# PMIC_USB.net
KiCad netlist of a schematic drawn in Altium Designer
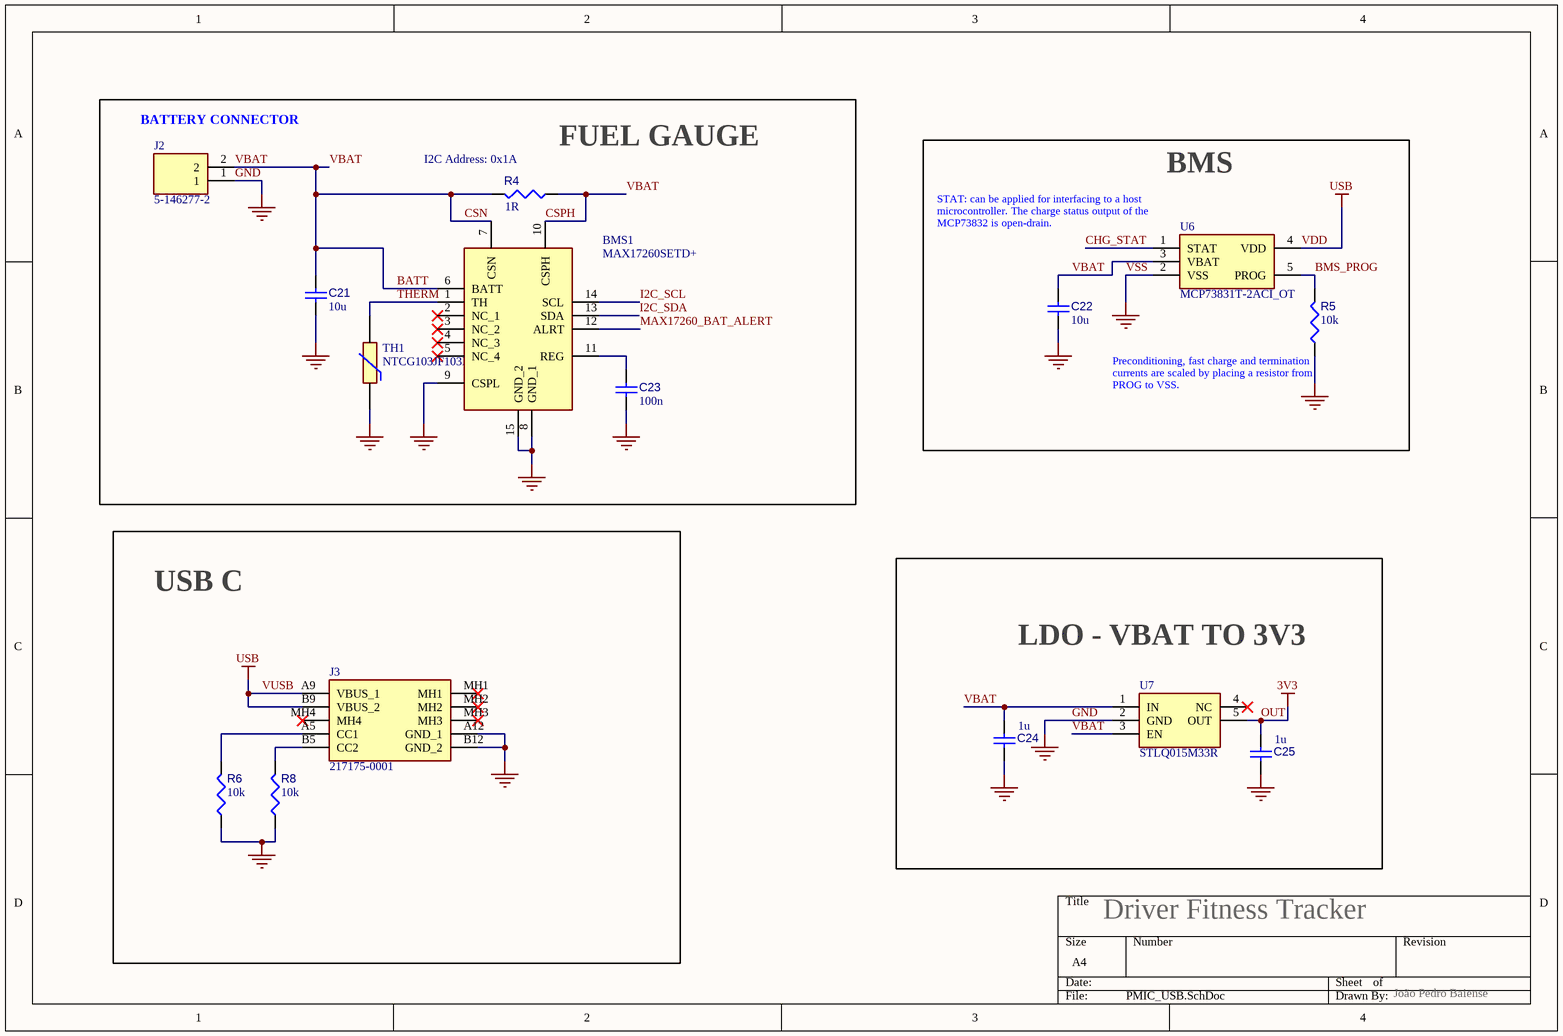
[diagram p0: PMIC_USB.SchDoc]

(export (version "E")
  (design (tool "Eeschema 10.0.6"))
  (components
    (comp (ref "BMS1")
      (value "MAX17260SETD+")
      (footprint "SON40P300X300X80-15N")
      (fields
        (field (name "MOUSER PART NUMBER") "700-MAX17260SETD+")
        (field (name "JLCPCB PART #") "C350946")
      )
      (libsource (lib "Tese_SymbolLib") (part "MAX17260SETD+"))
    )
    (comp (ref "C21")
      (value "10u")
      (footprint "CAPC1608X90X40NL10T20")
      (description "Multilayer Ceramic Capacitors MLCC - SMD/SMT NEW GLOBAL PN KGM15CR51C106MT 0603")
      (fields (field (name "TOLERANCE") "10%") (field (name "JLCPCB PART #") "C19702"))
      (libsource (lib "Tese_project") (part "CAP-NP-2"))
    )
    (comp (ref "C22")
      (value "10u")
      (footprint "CAPC1608X90X40NL10T20")
      (description "Multilayer Ceramic Capacitors MLCC - SMD/SMT NEW GLOBAL PN KGM15CR51C106MT 0603")
      (fields (field (name "TOLERANCE") "10%") (field (name "JLCPCB PART #") "C19702"))
      (libsource (lib "Tese_project") (part "CAP-NP-2"))
    )
    (comp (ref "C23")
      (value "100n")
      (footprint "CAPC1608X90X40NL10T20")
      (description "Multilayer Ceramic Capacitors MLCC - SMD/SMT 50V 0.1 uF X7R 0603 10% AEC-Q200")
      (fields (field (name "TOLERANCE") "10%") (field (name "JLCPCB PART #") "C1523"))
      (libsource (lib "Tese_project") (part "CAP-NP-2"))
    )
    (comp (ref "C24")
      (value "1u")
      (footprint "CAPC1608X90X40NL10T20")
      (description "Multilayer Ceramic Capacitors MLCC - SMD/SMT 50V 1uF X7R 0603 10%")
      (fields (field (name "TOLERANCE") "10%") (field (name "JLCPCB PART #") "C15849"))
      (libsource (lib "Tese_project") (part "CAP-NP-2"))
    )
    (comp (ref "C25")
      (value "1u")
      (footprint "CAPC1608X90X40NL10T20")
      (description "Multilayer Ceramic Capacitors MLCC - SMD/SMT 50V 1uF X7R 0603 10%")
      (fields (field (name "TOLERANCE") "10%") (field (name "JLCPCB PART #") "C15849"))
      (libsource (lib "Tese_project") (part "CAP-NP-2"))
    )
    (comp (ref "J2")
      (value "5-146277-2")
      (footprint "HEADER_2PINS")
      (description "Headers & Wire Housings 2P HEADER GOLD 30u single row")
      (fields (field (name "MOUSER PART NUMBER") "571-5-146277-2"))
      (libsource (lib "Tese_SymbolLib") (part "BATT_CONN_1"))
    )
    (comp (ref "J3")
      (value "217175-0001")
      (footprint "USB_C_CONNECTOR")
      (description "USB Connectors Top-Mnt SMT 6Ckt Type C Rec Molex")
      (fields (field (name "MOUSER PART NUMBER") "538-217175-0001"))
      (libsource (lib "Tese_SymbolLib") (part "USB_C_CONNECTOR"))
    )
    (comp (ref "R4")
      (value "1R")
      (footprint "RESC0402(1005)_L")
      (description "Thin Film Resistors - SMD .1W 1.0ohm 1% 0402 50ppm")
      (fields (field (name "POWER") "63mW") (field (name "TOLERANCE") "1%"))
      (libsource (lib "Tese_project") (part "RES-2"))
    )
    (comp (ref "R5")
      (value "10k")
      (footprint "RESC0402(1005)_L")
      (description "Thin Film Resistors - SMD 1/16W 10K ohm 1% 50ppm")
      (fields (field (name "POWER") "63mW") (field (name "TOLERANCE") "1%"))
      (libsource (lib "Tese_project") (part "RES-2"))
    )
    (comp (ref "R6")
      (value "10k")
      (footprint "RESC0402(1005)_L")
      (description "Thin Film Resistors - SMD 1/16W 10K ohm 1% 50ppm")
      (fields (field (name "POWER") "63mW") (field (name "TOLERANCE") "1%"))
      (libsource (lib "Tese_project") (part "RES-2"))
    )
    (comp (ref "R8")
      (value "10k")
      (footprint "RESC0402(1005)_L")
      (description "Thin Film Resistors - SMD 1/16W 10K ohm 1% 50ppm")
      (fields (field (name "POWER") "63mW") (field (name "TOLERANCE") "1%"))
      (libsource (lib "Tese_project") (part "RES-2"))
    )
    (comp (ref "TH1")
      (value "NTCG103JF103FT1")
      (footprint "THRMC1005X55N")
      (description "NTC (Negative Temperature Coefficient) Thermistors THERMISTOR, NTC 10K OHM, 1%, 0402")
      (fields
        (field (name "MOUSER PART NUMBER") "810-NTCG103JF103FT1")
        (field (name "JLCPCB PART #") "C209959")
      )
      (libsource (lib "Tese_SymbolLib") (part "NTCG103JF103FT1"))
    )
    (comp (ref "U6")
      (value "MCP73831T-2ACI_OT")
      (footprint "SOT95P270X145-5N")
      (description "Battery Management Charge mgnt contr")
      (fields
        (field (name "MOUSER PART NUMBER") "579-MCP73831T-2ACIOT")
        (field (name "ARROW PART NUMBER") "MCP73831T-2ACI/OT")
      )
      (libsource (lib "Tese_SymbolLib") (part "MCP73831T-2ACI_OT"))
    )
    (comp (ref "U7")
      (value "STLQ015M33R")
      (footprint "SOT95P280X145-5N")
      (description "LDO Voltage Regulators 150 mA - ultra low quiescent current linear voltage regulator")
      (fields (field (name "MOUSER PART NUMBER") "511-STLQ015M33R") (field (name "JLCPCB PART #") "C136154"))
      (libsource (lib "Tese_SymbolLib") (part "STLQ015M33R"))
    )
  )
  (nets
    (net (code "1") (name "/BATT") (class "Default")
      (node (ref "BMS1") (pin "10") (pinfunction "CSPH_10") (pintype "passive"))
      (node (ref "BMS1") (pin "6") (pinfunction "BATT_6") (pintype "passive"))
      (node (ref "BMS1") (pin "7") (pinfunction "CSN_7") (pintype "passive"))
      (node (ref "C21") (pin "1") (pinfunction "1_1") (pintype "passive"))
      (node (ref "C22") (pin "1") (pinfunction "1_1") (pintype "passive"))
      (node (ref "C24") (pin "1") (pinfunction "1_1") (pintype "passive"))
      (node (ref "J2") (pin "2") (pinfunction "2_2") (pintype "passive"))
      (node (ref "R4") (pin "1") (pinfunction "1_1") (pintype "passive"))
      (node (ref "R4") (pin "2") (pinfunction "2_2") (pintype "passive"))
      (node (ref "U6") (pin "3") (pinfunction "VBAT_3") (pintype "passive"))
      (node (ref "U7") (pin "1") (pinfunction "IN_1") (pintype "passive"))
      (node (ref "U7") (pin "3") (pinfunction "EN_3") (pintype "passive"))
    )
    (net (code "2") (name "/BMS_PROG") (class "Default")
      (node (ref "R5") (pin "2") (pinfunction "2_2") (pintype "passive"))
      (node (ref "U6") (pin "5") (pinfunction "PROG_5") (pintype "passive"))
    )
    (net (code "3") (name "/CHG_STAT") (class "Default")
      (node (ref "U6") (pin "1") (pinfunction "STAT_1") (pintype "passive"))
    )
    (net (code "4") (name "/I2C_SCL") (class "Default")
      (node (ref "BMS1") (pin "14") (pinfunction "SCL_14") (pintype "passive"))
    )
    (net (code "5") (name "/I2C_SDA") (class "Default")
      (node (ref "BMS1") (pin "13") (pinfunction "SDA_13") (pintype "passive"))
    )
    (net (code "6") (name "/MAX17260_BAT_ALERT") (class "Default")
      (node (ref "BMS1") (pin "12") (pinfunction "ALRT_12") (pintype "passive"))
    )
    (net (code "7") (name "/THERM") (class "Default")
      (node (ref "BMS1") (pin "1") (pinfunction "TH_1") (pintype "passive"))
      (node (ref "TH1") (pin "2") (pinfunction "2_2") (pintype "passive"))
    )
    (net (code "8") (name "3V3") (class "Default")
      (node (ref "C25") (pin "1") (pinfunction "1_1") (pintype "passive"))
      (node (ref "U7") (pin "5") (pinfunction "OUT_5") (pintype "passive"))
    )
    (net (code "9") (name "GND") (class "Default")
      (node (ref "BMS1") (pin "15") (pinfunction "GND_2_15") (pintype "passive"))
      (node (ref "BMS1") (pin "8") (pinfunction "GND_1_8") (pintype "passive"))
      (node (ref "BMS1") (pin "9") (pinfunction "CSPL_9") (pintype "passive"))
      (node (ref "C21") (pin "2") (pinfunction "2_2") (pintype "passive"))
      (node (ref "C22") (pin "2") (pinfunction "2_2") (pintype "passive"))
      (node (ref "C23") (pin "1") (pinfunction "1_1") (pintype "passive"))
      (node (ref "C24") (pin "2") (pinfunction "2_2") (pintype "passive"))
      (node (ref "C25") (pin "2") (pinfunction "2_2") (pintype "passive"))
      (node (ref "J2") (pin "1") (pinfunction "1_1") (pintype "passive"))
      (node (ref "J3") (pin "A12") (pinfunction "GND_1_A12") (pintype "passive"))
      (node (ref "J3") (pin "B12") (pinfunction "GND_2_B12") (pintype "passive"))
      (node (ref "R5") (pin "1") (pinfunction "1_1") (pintype "passive"))
      (node (ref "R6") (pin "1") (pinfunction "1_1") (pintype "passive"))
      (node (ref "R8") (pin "1") (pinfunction "1_1") (pintype "passive"))
      (node (ref "TH1") (pin "1") (pinfunction "1_1") (pintype "passive"))
      (node (ref "U6") (pin "2") (pinfunction "VSS_2") (pintype "passive"))
      (node (ref "U7") (pin "2") (pinfunction "GND_2") (pintype "passive"))
    )
    (net (code "10") (name "Net-(BMS1-REG)") (class "Default")
      (node (ref "BMS1") (pin "11") (pinfunction "REG_11") (pintype "passive"))
      (node (ref "C23") (pin "2") (pinfunction "2_2") (pintype "passive"))
    )
    (net (code "11") (name "Net-(J3-CC1)") (class "Default")
      (node (ref "J3") (pin "A5") (pinfunction "CC1_A5") (pintype "passive"))
      (node (ref "R6") (pin "2") (pinfunction "2_2") (pintype "passive"))
    )
    (net (code "12") (name "Net-(J3-CC2)") (class "Default")
      (node (ref "J3") (pin "B5") (pinfunction "CC2_B5") (pintype "passive"))
      (node (ref "R8") (pin "2") (pinfunction "2_2") (pintype "passive"))
    )
    (net (code "13") (name "USB") (class "Default")
      (node (ref "J3") (pin "A9") (pinfunction "VBUS_1_A9") (pintype "passive"))
      (node (ref "J3") (pin "B9") (pinfunction "VBUS_2_B9") (pintype "passive"))
      (node (ref "U6") (pin "4") (pinfunction "VDD_4") (pintype "passive"))
    )
    (net (code "14") (name "unconnected-(BMS1-NC_1-Pad2)") (class "Default")
      (node (ref "BMS1") (pin "2") (pinfunction "NC_1_2") (pintype "passive+no_connect"))
    )
    (net (code "15") (name "unconnected-(BMS1-NC_2-Pad3)") (class "Default")
      (node (ref "BMS1") (pin "3") (pinfunction "NC_2_3") (pintype "passive+no_connect"))
    )
    (net (code "16") (name "unconnected-(BMS1-NC_3-Pad4)") (class "Default")
      (node (ref "BMS1") (pin "4") (pinfunction "NC_3_4") (pintype "passive+no_connect"))
    )
    (net (code "17") (name "unconnected-(BMS1-NC_4-Pad5)") (class "Default")
      (node (ref "BMS1") (pin "5") (pinfunction "NC_4_5") (pintype "passive+no_connect"))
    )
    (net (code "18") (name "unconnected-(J3-PadMH1)") (class "Default")
      (node (ref "J3") (pin "MH1") (pinfunction "MH1_MH1") (pintype "passive+no_connect"))
    )
    (net (code "19") (name "unconnected-(J3-PadMH2)") (class "Default")
      (node (ref "J3") (pin "MH2") (pinfunction "MH2_MH2") (pintype "passive+no_connect"))
    )
    (net (code "20") (name "unconnected-(J3-PadMH3)") (class "Default")
      (node (ref "J3") (pin "MH3") (pinfunction "MH3_MH3") (pintype "passive+no_connect"))
    )
    (net (code "21") (name "unconnected-(J3-PadMH4)") (class "Default")
      (node (ref "J3") (pin "MH4") (pinfunction "MH4_MH4") (pintype "passive+no_connect"))
    )
    (net (code "22") (name "unconnected-(U7-NC-Pad4)") (class "Default")
      (node (ref "U7") (pin "4") (pinfunction "NC_4") (pintype "passive+no_connect"))
    )
  )
)
